# RadioMusic_F.net
KiCad netlist of a schematic drawn in EAGLE
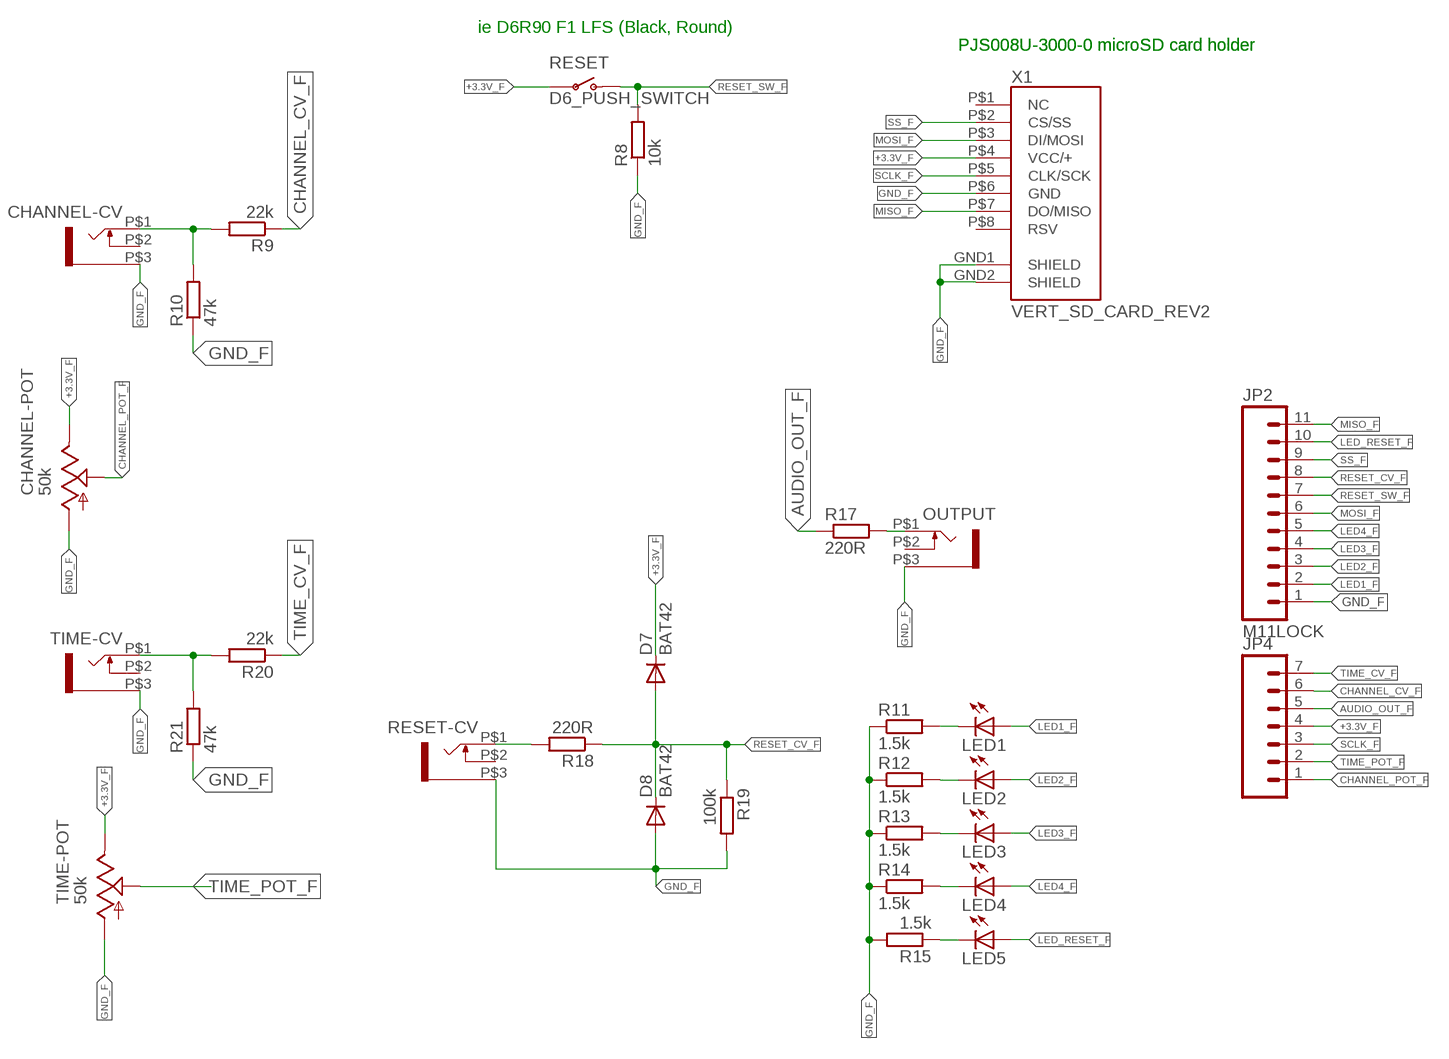
[diagram p0: schematic, sheet 1]

(export (version "E")
  (design (tool "Eeschema 10.0.6"))
  (components
    (comp (ref "CHANNEL-CV")
      (value "WQP-PJ301M-12_JACK")
      (footprint "eagle-import:WQP-PJ301M-12_JACK")
      (libsource (lib "eagle-import") (part "WQP-PJ301M-12_JACK"))
    )
    (comp (ref "CHANNEL-POT")
      (value "50k")
      (footprint "eagle-import:EVUF")
      (libsource (lib "eagle-import") (part "ALPHA-9MMAF2"))
    )
    (comp (ref "D7")
      (value "BAT42")
      (footprint "eagle-import:DO34-7")
      (libsource (lib "eagle-import") (part "BAT81"))
    )
    (comp (ref "D8")
      (value "BAT42")
      (footprint "eagle-import:DO34-7")
      (libsource (lib "eagle-import") (part "BAT81"))
    )
    (comp (ref "JP2")
      (value "M11LOCK")
      (footprint "eagle-import:1X11_LOCK")
      (libsource (lib "eagle-import") (part "M11LOCK"))
    )
    (comp (ref "JP4")
      (value "M07LOCK")
      (footprint "eagle-import:1X07_LOCK")
      (libsource (lib "eagle-import") (part "M07LOCK"))
    )
    (comp (ref "LED1")
      (value "LED3MM")
      (footprint "eagle-import:LED3MM")
      (libsource (lib "eagle-import") (part "LED3MM"))
    )
    (comp (ref "LED2")
      (value "LED3MM")
      (footprint "eagle-import:LED3MM")
      (libsource (lib "eagle-import") (part "LED3MM"))
    )
    (comp (ref "LED3")
      (value "LED3MM")
      (footprint "eagle-import:LED3MM")
      (libsource (lib "eagle-import") (part "LED3MM"))
    )
    (comp (ref "LED4")
      (value "LED3MM")
      (footprint "eagle-import:LED3MM")
      (libsource (lib "eagle-import") (part "LED3MM"))
    )
    (comp (ref "LED5")
      (value "LED3MM")
      (footprint "eagle-import:LED3MM")
      (libsource (lib "eagle-import") (part "LED3MM"))
    )
    (comp (ref "OUTPUT")
      (value "WQP-PJ301M-12_JACK")
      (footprint "eagle-import:WQP-PJ301M-12_JACK")
      (libsource (lib "eagle-import") (part "WQP-PJ301M-12_JACK"))
    )
    (comp (ref "R8")
      (value "10k")
      (footprint "eagle-import:0207_10")
      (libsource (lib "eagle-import") (part "R-EU_STANDARD_RESISTOR"))
    )
    (comp (ref "R9")
      (value "22k")
      (footprint "eagle-import:0207_10")
      (libsource (lib "eagle-import") (part "R-EU_STANDARD_RESISTOR"))
    )
    (comp (ref "R10")
      (value "47k")
      (footprint "eagle-import:0207_10")
      (libsource (lib "eagle-import") (part "R-EU_STANDARD_RESISTOR"))
    )
    (comp (ref "R11")
      (value "1.5k")
      (footprint "eagle-import:0207_10")
      (libsource (lib "eagle-import") (part "R-EU_STANDARD_RESISTOR"))
    )
    (comp (ref "R12")
      (value "1.5k")
      (footprint "eagle-import:0207_10")
      (libsource (lib "eagle-import") (part "R-EU_STANDARD_RESISTOR"))
    )
    (comp (ref "R13")
      (value "1.5k")
      (footprint "eagle-import:0207_10")
      (libsource (lib "eagle-import") (part "R-EU_STANDARD_RESISTOR"))
    )
    (comp (ref "R14")
      (value "1.5k")
      (footprint "eagle-import:0207_10")
      (libsource (lib "eagle-import") (part "R-EU_STANDARD_RESISTOR"))
    )
    (comp (ref "R15")
      (value "1.5k")
      (footprint "eagle-import:0207_10")
      (libsource (lib "eagle-import") (part "R-EU_STANDARD_RESISTOR"))
    )
    (comp (ref "R17")
      (value "220R")
      (footprint "eagle-import:0207_10")
      (libsource (lib "eagle-import") (part "R-EU_STANDARD_RESISTOR"))
    )
    (comp (ref "R18")
      (value "220R")
      (footprint "eagle-import:0207_10")
      (libsource (lib "eagle-import") (part "R-EU_STANDARD_RESISTOR"))
    )
    (comp (ref "R19")
      (value "100k")
      (footprint "eagle-import:0207_10")
      (libsource (lib "eagle-import") (part "R-EU_STANDARD_RESISTOR"))
    )
    (comp (ref "R20")
      (value "22k")
      (footprint "eagle-import:0207_10")
      (libsource (lib "eagle-import") (part "R-EU_STANDARD_RESISTOR"))
    )
    (comp (ref "R21")
      (value "47k")
      (footprint "eagle-import:0207_10")
      (libsource (lib "eagle-import") (part "R-EU_STANDARD_RESISTOR"))
    )
    (comp (ref "RESET")
      (value "D6_PUSH_SWITCH")
      (footprint "eagle-import:D6_BUTTON_RND")
      (libsource (lib "eagle-import") (part "D6_PUSH_SWITCH"))
    )
    (comp (ref "RESET-CV")
      (value "WQP-PJ301M-12_JACK")
      (footprint "eagle-import:WQP-PJ301M-12_JACK")
      (libsource (lib "eagle-import") (part "WQP-PJ301M-12_JACK"))
    )
    (comp (ref "TIME-CV")
      (value "WQP-PJ301M-12_JACK")
      (footprint "eagle-import:WQP-PJ301M-12_JACK")
      (libsource (lib "eagle-import") (part "WQP-PJ301M-12_JACK"))
    )
    (comp (ref "TIME-POT")
      (value "50k")
      (footprint "eagle-import:EVUF")
      (libsource (lib "eagle-import") (part "ALPHA-9MMAF2"))
    )
    (comp (ref "X1")
      (value "VERT_SD_CARD_REV2")
      (footprint "eagle-import:VERT_MICROSD_REV2")
      (libsource (lib "eagle-import") (part "VERT_SD_CARD_REV2"))
    )
  )
  (nets
    (net (code "1") (name "+3.3V_F") (class "Default")
      (node (ref "CHANNEL-POT") (pin "3") (pinfunction "E_3") (pintype "passive"))
      (node (ref "D7") (pin "C") (pinfunction "C_C") (pintype "passive"))
      (node (ref "JP4") (pin "4") (pinfunction "4_4") (pintype "passive"))
      (node (ref "RESET") (pin "P$3") (pinfunction "P_P$3") (pintype "passive"))
      (node (ref "RESET") (pin "P$4") (pinfunction "P_P$4") (pintype "passive"))
      (node (ref "TIME-POT") (pin "3") (pinfunction "E_3") (pintype "passive"))
      (node (ref "X1") (pin "P$4") (pinfunction "VCC/+_P$4") (pintype "bidirectional"))
    )
    (net (code "2") (name "AUDIO_OUT_F") (class "Default")
      (node (ref "JP4") (pin "5") (pinfunction "5_5") (pintype "passive"))
      (node (ref "R17") (pin "1") (pinfunction "1_1") (pintype "passive"))
    )
    (net (code "3") (name "CHANNEL_CV_F") (class "Default")
      (node (ref "JP4") (pin "6") (pinfunction "6_6") (pintype "passive"))
      (node (ref "R9") (pin "1") (pinfunction "1_1") (pintype "passive"))
    )
    (net (code "4") (name "CHANNEL_POT_F") (class "Default")
      (node (ref "CHANNEL-POT") (pin "2") (pinfunction "S_2") (pintype "passive"))
      (node (ref "JP4") (pin "1") (pinfunction "1_1") (pintype "passive"))
    )
    (net (code "5") (name "GND_F") (class "Default")
      (node (ref "CHANNEL-CV") (pin "P$3") (pinfunction "1_P$3") (pintype "passive"))
      (node (ref "CHANNEL-POT") (pin "1") (pinfunction "A_1") (pintype "passive"))
      (node (ref "D8") (pin "A") (pinfunction "A_A") (pintype "passive"))
      (node (ref "JP2") (pin "1") (pinfunction "1_1") (pintype "passive"))
      (node (ref "OUTPUT") (pin "P$3") (pinfunction "1_P$3") (pintype "passive"))
      (node (ref "R10") (pin "1") (pinfunction "1_1") (pintype "passive"))
      (node (ref "R11") (pin "1") (pinfunction "1_1") (pintype "passive"))
      (node (ref "R12") (pin "1") (pinfunction "1_1") (pintype "passive"))
      (node (ref "R13") (pin "1") (pinfunction "1_1") (pintype "passive"))
      (node (ref "R14") (pin "1") (pinfunction "1_1") (pintype "passive"))
      (node (ref "R15") (pin "2") (pinfunction "2_2") (pintype "passive"))
      (node (ref "R19") (pin "2") (pinfunction "2_2") (pintype "passive"))
      (node (ref "R21") (pin "1") (pinfunction "1_1") (pintype "passive"))
      (node (ref "R8") (pin "1") (pinfunction "1_1") (pintype "passive"))
      (node (ref "RESET-CV") (pin "P$3") (pinfunction "1_P$3") (pintype "passive"))
      (node (ref "TIME-CV") (pin "P$3") (pinfunction "1_P$3") (pintype "passive"))
      (node (ref "TIME-POT") (pin "1") (pinfunction "A_1") (pintype "passive"))
      (node (ref "X1") (pin "GND1") (pinfunction "SHIELD_GND1") (pintype "bidirectional"))
      (node (ref "X1") (pin "GND2") (pinfunction "SHIELD_GND2") (pintype "bidirectional"))
      (node (ref "X1") (pin "P$6") (pinfunction "GND_P$6") (pintype "bidirectional"))
    )
    (net (code "6") (name "LED1_F") (class "Default")
      (node (ref "JP2") (pin "2") (pinfunction "2_2") (pintype "passive"))
      (node (ref "LED1") (pin "A") (pinfunction "A_A") (pintype "passive"))
    )
    (net (code "7") (name "LED2_F") (class "Default")
      (node (ref "JP2") (pin "3") (pinfunction "3_3") (pintype "passive"))
      (node (ref "LED2") (pin "A") (pinfunction "A_A") (pintype "passive"))
    )
    (net (code "8") (name "LED3_F") (class "Default")
      (node (ref "JP2") (pin "4") (pinfunction "4_4") (pintype "passive"))
      (node (ref "LED3") (pin "A") (pinfunction "A_A") (pintype "passive"))
    )
    (net (code "9") (name "LED4_F") (class "Default")
      (node (ref "JP2") (pin "5") (pinfunction "5_5") (pintype "passive"))
      (node (ref "LED4") (pin "A") (pinfunction "A_A") (pintype "passive"))
    )
    (net (code "10") (name "LED_RESET_F") (class "Default")
      (node (ref "JP2") (pin "10") (pinfunction "10_10") (pintype "passive"))
      (node (ref "LED5") (pin "A") (pinfunction "A_A") (pintype "passive"))
    )
    (net (code "11") (name "MISO_F") (class "Default")
      (node (ref "JP2") (pin "11") (pinfunction "11_11") (pintype "passive"))
      (node (ref "X1") (pin "P$7") (pinfunction "DO/MISO_P$7") (pintype "bidirectional"))
    )
    (net (code "12") (name "MOSI_F") (class "Default")
      (node (ref "JP2") (pin "6") (pinfunction "6_6") (pintype "passive"))
      (node (ref "X1") (pin "P$3") (pinfunction "DI/MOSI_P$3") (pintype "bidirectional"))
    )
    (net (code "13") (name "Net-(CHANNEL-CV-2)") (class "Default")
      (node (ref "CHANNEL-CV") (pin "P$1") (pinfunction "2_P$1") (pintype "passive"))
      (node (ref "R10") (pin "2") (pinfunction "2_2") (pintype "passive"))
      (node (ref "R9") (pin "2") (pinfunction "2_2") (pintype "passive"))
    )
    (net (code "14") (name "Net-(LED1-C)") (class "Default")
      (node (ref "LED1") (pin "K") (pinfunction "C_K") (pintype "passive"))
      (node (ref "R11") (pin "2") (pinfunction "2_2") (pintype "passive"))
    )
    (net (code "15") (name "Net-(LED2-C)") (class "Default")
      (node (ref "LED2") (pin "K") (pinfunction "C_K") (pintype "passive"))
      (node (ref "R12") (pin "2") (pinfunction "2_2") (pintype "passive"))
    )
    (net (code "16") (name "Net-(LED3-C)") (class "Default")
      (node (ref "LED3") (pin "K") (pinfunction "C_K") (pintype "passive"))
      (node (ref "R13") (pin "2") (pinfunction "2_2") (pintype "passive"))
    )
    (net (code "17") (name "Net-(LED4-C)") (class "Default")
      (node (ref "LED4") (pin "K") (pinfunction "C_K") (pintype "passive"))
      (node (ref "R14") (pin "2") (pinfunction "2_2") (pintype "passive"))
    )
    (net (code "18") (name "Net-(LED5-C)") (class "Default")
      (node (ref "LED5") (pin "K") (pinfunction "C_K") (pintype "passive"))
      (node (ref "R15") (pin "1") (pinfunction "1_1") (pintype "passive"))
    )
    (net (code "19") (name "Net-(OUTPUT-2)") (class "Default")
      (node (ref "OUTPUT") (pin "P$1") (pinfunction "2_P$1") (pintype "passive"))
      (node (ref "R17") (pin "2") (pinfunction "2_2") (pintype "passive"))
    )
    (net (code "20") (name "Net-(RESET-CV-2)") (class "Default")
      (node (ref "R18") (pin "2") (pinfunction "2_2") (pintype "passive"))
      (node (ref "RESET-CV") (pin "P$1") (pinfunction "2_P$1") (pintype "passive"))
    )
    (net (code "21") (name "Net-(TIME-CV-2)") (class "Default")
      (node (ref "R20") (pin "2") (pinfunction "2_2") (pintype "passive"))
      (node (ref "R21") (pin "2") (pinfunction "2_2") (pintype "passive"))
      (node (ref "TIME-CV") (pin "P$1") (pinfunction "2_P$1") (pintype "passive"))
    )
    (net (code "22") (name "RESET_CV_F") (class "Default")
      (node (ref "D7") (pin "A") (pinfunction "A_A") (pintype "passive"))
      (node (ref "D8") (pin "C") (pinfunction "C_C") (pintype "passive"))
      (node (ref "JP2") (pin "8") (pinfunction "8_8") (pintype "passive"))
      (node (ref "R18") (pin "1") (pinfunction "1_1") (pintype "passive"))
      (node (ref "R19") (pin "1") (pinfunction "1_1") (pintype "passive"))
    )
    (net (code "23") (name "RESET_SW_F") (class "Default")
      (node (ref "JP2") (pin "7") (pinfunction "7_7") (pintype "passive"))
      (node (ref "R8") (pin "2") (pinfunction "2_2") (pintype "passive"))
      (node (ref "RESET") (pin "P$1") (pinfunction "O_P$1") (pintype "passive"))
      (node (ref "RESET") (pin "P$2") (pinfunction "O_P$2") (pintype "passive"))
    )
    (net (code "24") (name "SCLK_F") (class "Default")
      (node (ref "JP4") (pin "3") (pinfunction "3_3") (pintype "passive"))
      (node (ref "X1") (pin "P$5") (pinfunction "CLK/SCK_P$5") (pintype "bidirectional"))
    )
    (net (code "25") (name "SS_F") (class "Default")
      (node (ref "JP2") (pin "9") (pinfunction "9_9") (pintype "passive"))
      (node (ref "X1") (pin "P$2") (pinfunction "CS/SS_P$2") (pintype "bidirectional"))
    )
    (net (code "26") (name "TIME_CV_F") (class "Default")
      (node (ref "JP4") (pin "7") (pinfunction "7_7") (pintype "passive"))
      (node (ref "R20") (pin "1") (pinfunction "1_1") (pintype "passive"))
    )
    (net (code "27") (name "TIME_POT_F") (class "Default")
      (node (ref "JP4") (pin "2") (pinfunction "2_2") (pintype "passive"))
      (node (ref "TIME-POT") (pin "2") (pinfunction "S_2") (pintype "passive"))
    )
    (net (code "28") (name "unconnected-(CHANNEL-CV-3-PadP$2)") (class "Default")
      (node (ref "CHANNEL-CV") (pin "P$2") (pinfunction "3_P$2") (pintype "passive"))
    )
    (net (code "29") (name "unconnected-(OUTPUT-3-PadP$2)") (class "Default")
      (node (ref "OUTPUT") (pin "P$2") (pinfunction "3_P$2") (pintype "passive"))
    )
    (net (code "30") (name "unconnected-(RESET-CV-3-PadP$2)") (class "Default")
      (node (ref "RESET-CV") (pin "P$2") (pinfunction "3_P$2") (pintype "passive"))
    )
    (net (code "31") (name "unconnected-(TIME-CV-3-PadP$2)") (class "Default")
      (node (ref "TIME-CV") (pin "P$2") (pinfunction "3_P$2") (pintype "passive"))
    )
    (net (code "32") (name "unconnected-(X1-NC-PadP$1)") (class "Default")
      (node (ref "X1") (pin "P$1") (pinfunction "NC_P$1") (pintype "bidirectional"))
    )
    (net (code "33") (name "unconnected-(X1-RSV-PadP$8)") (class "Default")
      (node (ref "X1") (pin "P$8") (pinfunction "RSV_P$8") (pintype "bidirectional"))
    )
  )
)
